# int_req.net
KiCad netlist of a schematic drawn in Altium Designer
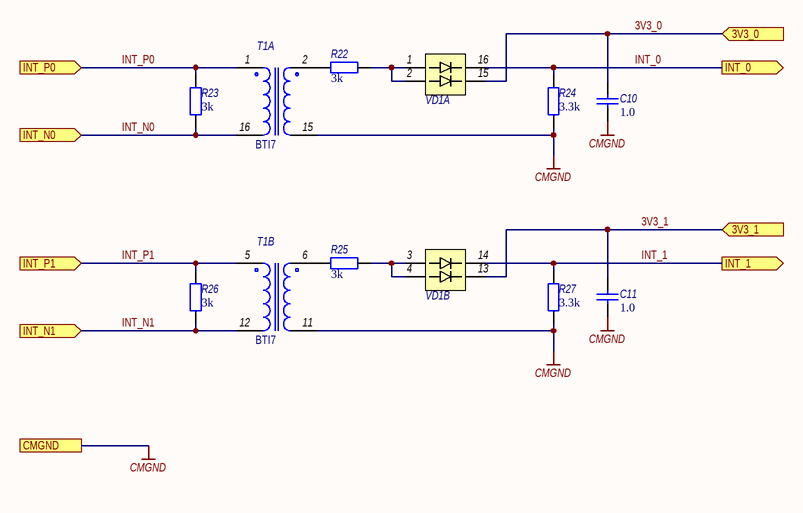
[diagram p0: int_req.SchDoc]

(export (version "E")
  (design (tool "Eeschema 10.0.6"))
  (components
    (comp (ref "C10")
      (value "1.0")
      (footprint "SMD_0805")
      (description "Capacitor")
      (fields (field (name "PUBLISHER") "Altium Limited"))
      (libsource (lib "Capacitor") (part "Capacitor"))
    )
    (comp (ref "C11")
      (value "1.0")
      (footprint "SMD_0805")
      (description "Capacitor")
      (fields (field (name "PUBLISHER") "Altium Limited"))
      (libsource (lib "Capacitor") (part "Capacitor"))
    )
    (comp (ref "R22")
      (value "3k")
      (footprint "SMD_0805")
      (description "Resistor")
      (fields (field (name "PUBLISHER") "Altium Limited"))
      (libsource (lib "") (part "Resistor_1"))
    )
    (comp (ref "R23")
      (value "3k")
      (footprint "SMD_0805")
      (description "Resistor")
      (fields (field (name "PUBLISHER") "Altium Limited"))
      (libsource (lib "Resistor") (part "Resistor"))
    )
    (comp (ref "R24")
      (value "3.3k")
      (footprint "SMD_0805")
      (description "Resistor")
      (fields (field (name "PUBLISHER") "Altium Limited"))
      (libsource (lib "Resistor") (part "Resistor"))
    )
    (comp (ref "R25")
      (value "3k")
      (footprint "SMD_0805")
      (description "Resistor")
      (fields (field (name "PUBLISHER") "Altium Limited"))
      (libsource (lib "") (part "Resistor_1"))
    )
    (comp (ref "R26")
      (value "3k")
      (footprint "SMD_0805")
      (description "Resistor")
      (fields (field (name "PUBLISHER") "Altium Limited"))
      (libsource (lib "Resistor") (part "Resistor"))
    )
    (comp (ref "R27")
      (value "3.3k")
      (footprint "SMD_0805")
      (description "Resistor")
      (fields (field (name "PUBLISHER") "Altium Limited"))
      (libsource (lib "Resistor") (part "Resistor"))
    )
    (comp (ref "T1")
      (value "BTI7")
      (footprint "BTI7")
      (description "Блок трансформаторов")
      (libsource (lib "BTI7") (part "BTI7"))
    )
    (comp (ref "VD1")
      (value "2DS627A OSM")
      (footprint "401.16-3")
      (description "Диодная матрица")
      (libsource (lib "Diod") (part "2DS627A_4p"))
    )
  )
  (nets
    (net (code "1") (name "/3V3_0") (class "Default")
      (node (ref "C10") (pin "2") (pinfunction "2_2") (pintype "passive"))
      (node (ref "VD1") (pin "15") (pinfunction "2B_15") (pintype "passive"))
    )
    (net (code "2") (name "/3V3_1") (class "Default")
      (node (ref "C11") (pin "2") (pinfunction "2_2") (pintype "passive"))
      (node (ref "VD1") (pin "13") (pinfunction "2D_13") (pintype "passive"))
    )
    (net (code "3") (name "/INT_0") (class "Default")
      (node (ref "R24") (pin "2") (pinfunction "2_2") (pintype "passive"))
      (node (ref "VD1") (pin "16") (pinfunction "2A_16") (pintype "passive"))
    )
    (net (code "4") (name "/INT_1") (class "Default")
      (node (ref "R27") (pin "2") (pinfunction "2_2") (pintype "passive"))
      (node (ref "VD1") (pin "14") (pinfunction "2C_14") (pintype "passive"))
    )
    (net (code "5") (name "/INT_N0") (class "Default")
      (node (ref "R23") (pin "1") (pinfunction "1_1") (pintype "passive"))
      (node (ref "T1") (pin "16") (pinfunction "16_16") (pintype "passive"))
    )
    (net (code "6") (name "/INT_N1") (class "Default")
      (node (ref "R26") (pin "1") (pinfunction "1_1") (pintype "passive"))
      (node (ref "T1") (pin "12") (pinfunction "12_12") (pintype "passive"))
    )
    (net (code "7") (name "/INT_P0") (class "Default")
      (node (ref "R23") (pin "2") (pinfunction "2_2") (pintype "passive"))
      (node (ref "T1") (pin "1") (pinfunction "1_1") (pintype "passive"))
    )
    (net (code "8") (name "/INT_P1") (class "Default")
      (node (ref "R26") (pin "2") (pinfunction "2_2") (pintype "passive"))
      (node (ref "T1") (pin "5") (pinfunction "5_5") (pintype "passive"))
    )
    (net (code "9") (name "CMGND") (class "Default")
      (node (ref "C10") (pin "1") (pinfunction "1_1") (pintype "passive"))
      (node (ref "C11") (pin "1") (pinfunction "1_1") (pintype "passive"))
      (node (ref "R24") (pin "1") (pinfunction "1_1") (pintype "passive"))
      (node (ref "R27") (pin "1") (pinfunction "1_1") (pintype "passive"))
      (node (ref "T1") (pin "11") (pinfunction "11_11") (pintype "passive"))
      (node (ref "T1") (pin "15") (pinfunction "15_15") (pintype "passive"))
    )
    (net (code "10") (name "Net-(R22-Pad2)") (class "Default")
      (node (ref "R22") (pin "2") (pinfunction "2_2") (pintype "passive"))
      (node (ref "T1") (pin "2") (pinfunction "2_2") (pintype "passive"))
    )
    (net (code "11") (name "Net-(R25-Pad2)") (class "Default")
      (node (ref "R25") (pin "2") (pinfunction "2_2") (pintype "passive"))
      (node (ref "T1") (pin "6") (pinfunction "6_6") (pintype "passive"))
    )
    (net (code "12") (name "Net-(VD1A-1A)") (class "Default")
      (node (ref "R22") (pin "1") (pinfunction "1_1") (pintype "passive"))
      (node (ref "VD1") (pin "1") (pinfunction "1A_1") (pintype "passive"))
      (node (ref "VD1") (pin "2") (pinfunction "1B_2") (pintype "passive"))
    )
    (net (code "13") (name "Net-(VD1B-1C)") (class "Default")
      (node (ref "R25") (pin "1") (pinfunction "1_1") (pintype "passive"))
      (node (ref "VD1") (pin "3") (pinfunction "1C_3") (pintype "passive"))
      (node (ref "VD1") (pin "4") (pinfunction "1D_4") (pintype "passive"))
    )
  )
)
